# rev5.net
KiCad netlist of a schematic drawn in Altium Designer
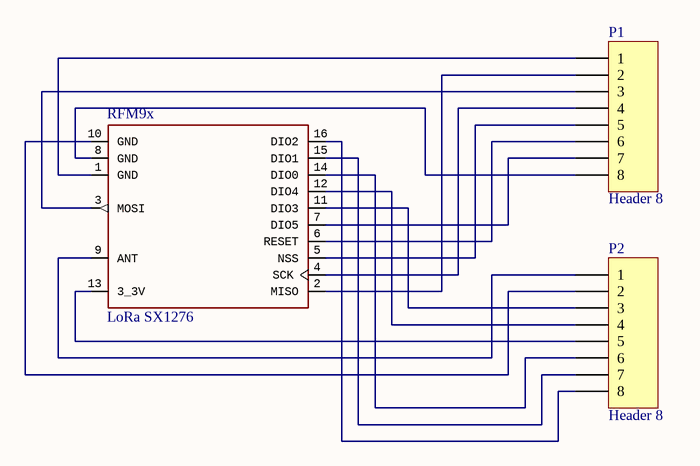
[diagram p0: rev5.SchDoc]

(export (version "E")
  (design (tool "Eeschema 10.0.6"))
  (components
    (comp (ref "P1")
      (value "Header 8")
      (footprint "HDR1X8")
      (description "Header, 8-Pin")
      (fields (field (name "PUBLISHER") "Altium Limited"))
      (libsource (lib "Miscellaneous Connectors") (part "Header 8"))
    )
    (comp (ref "P2")
      (value "Header 8")
      (footprint "HDR1X8")
      (description "Header, 8-Pin")
      (fields (field (name "PUBLISHER") "Altium Limited"))
      (libsource (lib "Miscellaneous Connectors") (part "Header 8"))
    )
    (comp (ref "RFM9x")
      (value "LoRa SX1276")
      (footprint "XCVR_RFM95W-868S2")
      (fields (field (name "MF") "RF") (field (name "MP") "RFM95W-868S2"))
      (libsource (lib "RFM95rev1") (part "RFM95W-868S2"))
    )
  )
  (nets
    (net (code "1") (name "Net-(P1-Pad1)") (class "Default")
      (node (ref "P1") (pin "1") (pinfunction "1_1") (pintype "passive"))
      (node (ref "RFM9x") (pin "1") (pinfunction "GND_1") (pintype "power_in"))
    )
    (net (code "2") (name "Net-(P1-Pad8)") (class "Default")
      (node (ref "P1") (pin "8") (pinfunction "8_8") (pintype "passive"))
      (node (ref "RFM9x") (pin "8") (pinfunction "GND_8") (pintype "power_in"))
    )
    (net (code "3") (name "Net-(P2-Pad2)") (class "Default")
      (node (ref "P2") (pin "2") (pinfunction "2_2") (pintype "passive"))
      (node (ref "RFM9x") (pin "10") (pinfunction "GND_10") (pintype "power_in"))
    )
    (net (code "4") (name "Net-(RFM9x-3_3V)") (class "Default")
      (node (ref "P2") (pin "5") (pinfunction "5_5") (pintype "passive"))
      (node (ref "RFM9x") (pin "13") (pinfunction "3_3V_13") (pintype "power_in"))
    )
    (net (code "5") (name "Net-(RFM9x-ANT)") (class "Default")
      (node (ref "P2") (pin "1") (pinfunction "1_1") (pintype "passive"))
      (node (ref "RFM9x") (pin "9") (pinfunction "ANT_9") (pintype "passive"))
    )
    (net (code "6") (name "Net-(RFM9x-DIO0)") (class "Default")
      (node (ref "P2") (pin "6") (pinfunction "6_6") (pintype "passive"))
      (node (ref "RFM9x") (pin "14") (pinfunction "DIO0_14") (pintype "passive"))
    )
    (net (code "7") (name "Net-(RFM9x-DIO1)") (class "Default")
      (node (ref "P2") (pin "7") (pinfunction "7_7") (pintype "passive"))
      (node (ref "RFM9x") (pin "15") (pinfunction "DIO1_15") (pintype "passive"))
    )
    (net (code "8") (name "Net-(RFM9x-DIO2)") (class "Default")
      (node (ref "P2") (pin "8") (pinfunction "8_8") (pintype "passive"))
      (node (ref "RFM9x") (pin "16") (pinfunction "DIO2_16") (pintype "passive"))
    )
    (net (code "9") (name "Net-(RFM9x-DIO3)") (class "Default")
      (node (ref "P2") (pin "3") (pinfunction "3_3") (pintype "passive"))
      (node (ref "RFM9x") (pin "11") (pinfunction "DIO3_11") (pintype "passive"))
    )
    (net (code "10") (name "Net-(RFM9x-DIO4)") (class "Default")
      (node (ref "P2") (pin "4") (pinfunction "4_4") (pintype "passive"))
      (node (ref "RFM9x") (pin "12") (pinfunction "DIO4_12") (pintype "passive"))
    )
    (net (code "11") (name "Net-(RFM9x-DIO5)") (class "Default")
      (node (ref "P1") (pin "7") (pinfunction "7_7") (pintype "passive"))
      (node (ref "RFM9x") (pin "7") (pinfunction "DIO5_7") (pintype "passive"))
    )
    (net (code "12") (name "Net-(RFM9x-MISO)") (class "Default")
      (node (ref "P1") (pin "2") (pinfunction "2_2") (pintype "passive"))
      (node (ref "RFM9x") (pin "2") (pinfunction "MISO_2") (pintype "passive"))
    )
    (net (code "13") (name "Net-(RFM9x-MOSI)") (class "Default")
      (node (ref "P1") (pin "3") (pinfunction "3_3") (pintype "passive"))
      (node (ref "RFM9x") (pin "3") (pinfunction "MOSI_3") (pintype "output"))
    )
    (net (code "14") (name "Net-(RFM9x-NSS)") (class "Default")
      (node (ref "P1") (pin "5") (pinfunction "5_5") (pintype "passive"))
      (node (ref "RFM9x") (pin "5") (pinfunction "NSS_5") (pintype "passive"))
    )
    (net (code "15") (name "Net-(RFM9x-RESET)") (class "Default")
      (node (ref "P1") (pin "6") (pinfunction "6_6") (pintype "passive"))
      (node (ref "RFM9x") (pin "6") (pinfunction "RESET_6") (pintype "passive"))
    )
    (net (code "16") (name "Net-(RFM9x-SCK)") (class "Default")
      (node (ref "P1") (pin "4") (pinfunction "4_4") (pintype "passive"))
      (node (ref "RFM9x") (pin "4") (pinfunction "SCK_4") (pintype "passive"))
    )
  )
)
